# touch.net
KiCad netlist of a schematic drawn in Altium Designer
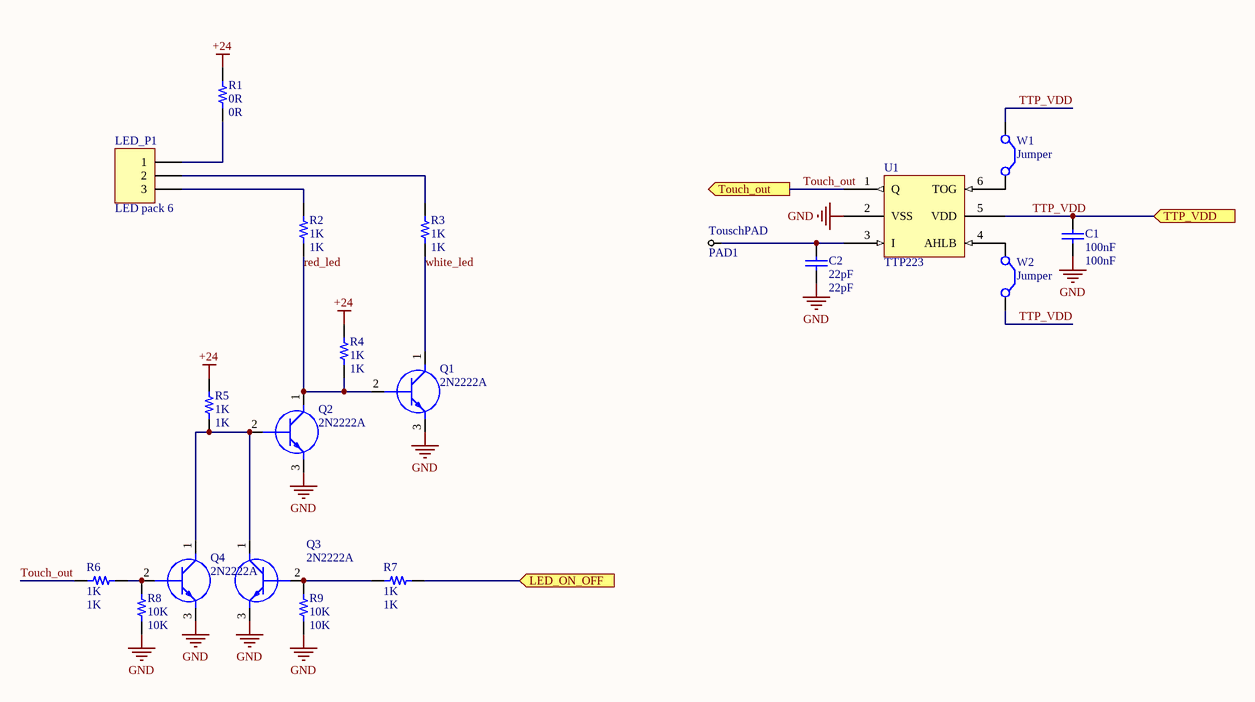
[diagram p0: touch.SchDoc]

(export (version "E")
  (design (tool "Eeschema 10.0.6"))
  (components
    (comp (ref "C1")
      (value "100nF")
      (footprint "0603C")
      (description "CAP SMD 0603")
      (fields (field (name "ALTIUM_VALUE") "100nF") (field (name "PUBLISHER") "Altium Limited"))
      (libsource (lib "Miscellaneous Devices") (part "Cap"))
    )
    (comp (ref "C2")
      (value "22pF")
      (footprint "0603C")
      (description "X7R_NPO")
      (fields (field (name "ALTIUM_VALUE") "22pF") (field (name "PUBLISHER") "Altium Limited"))
      (libsource (lib "Miscellaneous Devices") (part "Cap"))
    )
    (comp (ref "LED_P1")
      (value "LED pack 6")
      (footprint "ledpack6-b")
      (description "6led-red white LED pack")
      (fields (field (name "PUBLISHER") "Altium Limited"))
      (libsource (lib "Miscellaneous Connectors") (part "Header 3"))
    )
    (comp (ref "PAD1")
      (value "TouschPAD")
      (footprint "touchPAD2")
      (libsource (lib "Altium (2)") (part "Test Point"))
    )
    (comp (ref "Q1")
      (value "2N2222A")
      (footprint "soT95p280x130-3n")
      (description "Transistor BJT NPN SMD")
      (libsource (lib "*") (part "2N2222A"))
    )
    (comp (ref "Q2")
      (value "2N2222A")
      (footprint "soT95p280x130-3n")
      (description "Transistor BJT NPN SMD")
      (libsource (lib "*") (part "2N2222A"))
    )
    (comp (ref "Q3")
      (value "2N2222A")
      (footprint "soT95p280x130-3n")
      (description "Transistor BJT NPN SMD")
      (libsource (lib "*") (part "2N2222A"))
    )
    (comp (ref "Q4")
      (value "2N2222A")
      (footprint "soT95p280x130-3n")
      (description "Transistor BJT NPN SMD")
      (libsource (lib "*") (part "2N2222A"))
    )
    (comp (ref "R1")
      (value "0R")
      (footprint "0603R")
      (description "RES SMD 0603")
      (fields (field (name "PART NUMBER") "RCS0805100KFKEA") (field (name "ALTIUM_VALUE") "0R"))
      (libsource (lib "lamp control-ver2") (part "Resistor"))
    )
    (comp (ref "R2")
      (value "1K")
      (footprint "RES1812")
      (description "RES SMD 1812")
      (fields (field (name "PART NUMBER") "RCS0805100KFKEA") (field (name "ALTIUM_VALUE") "1K"))
      (libsource (lib "lamp control-ver2") (part "Resistor"))
    )
    (comp (ref "R3")
      (value "1K")
      (footprint "RES1812")
      (description "RES SMD 1812")
      (fields (field (name "PART NUMBER") "RCS0805100KFKEA") (field (name "ALTIUM_VALUE") "1K"))
      (libsource (lib "lamp control-ver2") (part "Resistor"))
    )
    (comp (ref "R4")
      (value "1K")
      (footprint "0603R")
      (description "RES SMD 0603")
      (fields (field (name "PART NUMBER") "RCS0805100KFKEA") (field (name "ALTIUM_VALUE") "1K"))
      (libsource (lib "lamp control-ver2") (part "Resistor"))
    )
    (comp (ref "R5")
      (value "1K")
      (footprint "0603R")
      (description "RES SMD 0603")
      (fields (field (name "PART NUMBER") "RCS0805100KFKEA") (field (name "ALTIUM_VALUE") "1K"))
      (libsource (lib "lamp control-ver2") (part "Resistor"))
    )
    (comp (ref "R6")
      (value "1K")
      (footprint "0603R")
      (description "RES SMD 0603")
      (fields (field (name "PART NUMBER") "RCS0805100KFKEA") (field (name "ALTIUM_VALUE") "1K"))
      (libsource (lib "lamp control-ver2") (part "Resistor"))
    )
    (comp (ref "R7")
      (value "1K")
      (footprint "0603R")
      (description "RES SMD 0603")
      (fields (field (name "PART NUMBER") "RCS0805100KFKEA") (field (name "ALTIUM_VALUE") "1K"))
      (libsource (lib "lamp control-ver2") (part "Resistor"))
    )
    (comp (ref "R8")
      (value "10K")
      (footprint "0603R")
      (description "RES SMD 0603")
      (fields (field (name "PART NUMBER") "RCS0805100KFKEA") (field (name "ALTIUM_VALUE") "10K"))
      (libsource (lib "lamp control-ver2") (part "Resistor"))
    )
    (comp (ref "R9")
      (value "10K")
      (footprint "0603R")
      (description "RES SMD 0603")
      (fields (field (name "PART NUMBER") "RCS0805100KFKEA") (field (name "ALTIUM_VALUE") "10K"))
      (libsource (lib "lamp control-ver2") (part "Resistor"))
    )
    (comp (ref "U1")
      (value "TTP223")
      (footprint "SOT23-6_L")
      (description "capacitive touch IC")
      (libsource (lib "Schlib1") (part "ttp223b"))
    )
    (comp (ref "W1")
      (value "Jumper")
      (footprint "JUMPER")
      (description "Jumper Wire")
      (fields (field (name "PUBLISHER") "Altium Limited"))
      (libsource (lib "Miscellaneous Devices") (part "Jumper"))
    )
    (comp (ref "W2")
      (value "Jumper")
      (footprint "JUMPER")
      (description "Jumper Wire")
      (fields (field (name "PUBLISHER") "Altium Limited"))
      (libsource (lib "Miscellaneous Devices") (part "Jumper"))
    )
  )
  (nets
    (net (code "1") (name "+24") (class "Default")
      (node (ref "R1") (pin "2") (pinfunction "2_2") (pintype "passive"))
      (node (ref "R4") (pin "1") (pinfunction "1_1") (pintype "passive"))
      (node (ref "R5") (pin "1") (pinfunction "1_1") (pintype "passive"))
    )
    (net (code "2") (name "/LED_ON_OFF") (class "Default")
      (node (ref "R7") (pin "2") (pinfunction "2_2") (pintype "passive"))
    )
    (net (code "3") (name "/TTP_VDD") (class "Default")
      (node (ref "C1") (pin "2") (pinfunction "2_2") (pintype "passive"))
      (node (ref "U1") (pin "5") (pinfunction "VDD_5") (pintype "power_in"))
      (node (ref "W1") (pin "1") (pinfunction "C1_1") (pintype "passive"))
      (node (ref "W2") (pin "2") (pinfunction "C2_2") (pintype "passive"))
    )
    (net (code "4") (name "/Touch_out") (class "Default")
      (node (ref "R6") (pin "1") (pinfunction "1_1") (pintype "passive"))
      (node (ref "U1") (pin "1") (pinfunction "Q_1") (pintype "output"))
    )
    (net (code "5") (name "/red_led") (class "Default")
      (node (ref "Q1") (pin "2") (pinfunction "B_2") (pintype "passive"))
      (node (ref "Q2") (pin "1") (pinfunction "C_1") (pintype "passive"))
      (node (ref "R2") (pin "2") (pinfunction "2_2") (pintype "passive"))
      (node (ref "R4") (pin "2") (pinfunction "2_2") (pintype "passive"))
    )
    (net (code "6") (name "/white_led") (class "Default")
      (node (ref "Q1") (pin "1") (pinfunction "C_1") (pintype "passive"))
      (node (ref "R3") (pin "2") (pinfunction "2_2") (pintype "passive"))
    )
    (net (code "7") (name "GND") (class "Default")
      (node (ref "C1") (pin "1") (pinfunction "1_1") (pintype "passive"))
      (node (ref "C2") (pin "1") (pinfunction "1_1") (pintype "passive"))
      (node (ref "Q1") (pin "3") (pinfunction "E_3") (pintype "passive"))
      (node (ref "Q2") (pin "3") (pinfunction "E_3") (pintype "passive"))
      (node (ref "Q3") (pin "3") (pinfunction "E_3") (pintype "passive"))
      (node (ref "Q4") (pin "3") (pinfunction "E_3") (pintype "passive"))
      (node (ref "R8") (pin "2") (pinfunction "2_2") (pintype "passive"))
      (node (ref "R9") (pin "2") (pinfunction "2_2") (pintype "passive"))
      (node (ref "U1") (pin "2") (pinfunction "VSS_2") (pintype "power_in"))
    )
    (net (code "8") (name "Net-(LED_P1-Pad1)") (class "Default")
      (node (ref "LED_P1") (pin "1") (pinfunction "1_1") (pintype "passive"))
      (node (ref "R1") (pin "1") (pinfunction "1_1") (pintype "passive"))
    )
    (net (code "9") (name "Net-(LED_P1-Pad2)") (class "Default")
      (node (ref "LED_P1") (pin "2") (pinfunction "2_2") (pintype "passive"))
      (node (ref "R3") (pin "1") (pinfunction "1_1") (pintype "passive"))
    )
    (net (code "10") (name "Net-(LED_P1-Pad3)") (class "Default")
      (node (ref "LED_P1") (pin "3") (pinfunction "3_3") (pintype "passive"))
      (node (ref "R2") (pin "1") (pinfunction "1_1") (pintype "passive"))
    )
    (net (code "11") (name "Net-(PAD1-T)") (class "Default")
      (node (ref "C2") (pin "2") (pinfunction "2_2") (pintype "passive"))
      (node (ref "PAD1") (pin "1") (pinfunction "T_1") (pintype "passive"))
      (node (ref "U1") (pin "3") (pinfunction "I_3") (pintype "input"))
    )
    (net (code "12") (name "Net-(Q2-B)") (class "Default")
      (node (ref "Q2") (pin "2") (pinfunction "B_2") (pintype "passive"))
      (node (ref "Q3") (pin "1") (pinfunction "C_1") (pintype "passive"))
      (node (ref "Q4") (pin "1") (pinfunction "C_1") (pintype "passive"))
      (node (ref "R5") (pin "2") (pinfunction "2_2") (pintype "passive"))
    )
    (net (code "13") (name "Net-(Q3-B)") (class "Default")
      (node (ref "Q3") (pin "2") (pinfunction "B_2") (pintype "passive"))
      (node (ref "R7") (pin "1") (pinfunction "1_1") (pintype "passive"))
      (node (ref "R9") (pin "1") (pinfunction "1_1") (pintype "passive"))
    )
    (net (code "14") (name "Net-(Q4-B)") (class "Default")
      (node (ref "Q4") (pin "2") (pinfunction "B_2") (pintype "passive"))
      (node (ref "R6") (pin "2") (pinfunction "2_2") (pintype "passive"))
      (node (ref "R8") (pin "1") (pinfunction "1_1") (pintype "passive"))
    )
    (net (code "15") (name "Net-(U1-AHLB)") (class "Default")
      (node (ref "U1") (pin "4") (pinfunction "AHLB_4") (pintype "input"))
      (node (ref "W2") (pin "1") (pinfunction "C1_1") (pintype "passive"))
    )
    (net (code "16") (name "Net-(U1-TOG)") (class "Default")
      (node (ref "U1") (pin "6") (pinfunction "TOG_6") (pintype "input"))
      (node (ref "W1") (pin "2") (pinfunction "C2_2") (pintype "passive"))
    )
  )
)
